# RX.net
KiCad netlist of a schematic drawn in EAGLE
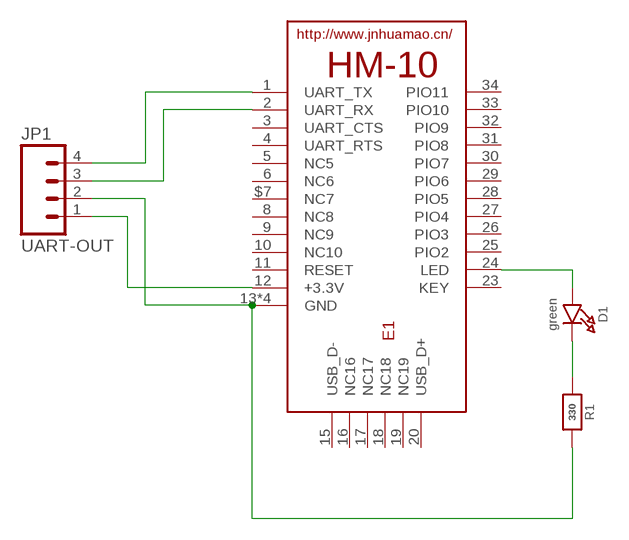
[diagram p0: schematic, sheet 1]

(export (version "E")
  (design (tool "Eeschema 10.0.6"))
  (components
    (comp (ref "D1")
      (value "green")
      (footprint "eagle-import:CHIPLED_0805_NOOUTLINE")
      (libsource (lib "eagle-import") (part "LED0805_NOOUTLINE"))
    )
    (comp (ref "E1")
      (value "HM-10-BOARD")
      (footprint "eagle-import:26.9X13X2.2_BOARD")
      (libsource (lib "eagle-import") (part "HM-10-BOARD"))
    )
    (comp (ref "JP1")
      (value "UART-OUT")
      (footprint "eagle-import:1X04")
      (libsource (lib "eagle-import") (part "M04PTH"))
    )
    (comp (ref "R1")
      (value "330")
      (footprint "eagle-import:0805-NO")
      (libsource (lib "eagle-import") (part "RESISTOR0805_NOOUTLINE"))
    )
  )
  (nets
    (net (code "1") (name "Net-(D1-PadC)") (class "Default")
      (node (ref "D1") (pin "C") (pinfunction "C_C") (pintype "passive"))
      (node (ref "R1") (pin "1") (pinfunction "1_1") (pintype "passive"))
    )
    (net (code "2") (name "Net-(E1-+3.3V)") (class "Default")
      (node (ref "E1") (pin "12") (pinfunction "+3.3V_12") (pintype "bidirectional"))
      (node (ref "JP1") (pin "1") (pinfunction "1_1") (pintype "passive"))
    )
    (net (code "3") (name "Net-(E1-GND-Pad13)") (class "Default")
      (node (ref "E1") (pin "13") (pinfunction "GND_13") (pintype "bidirectional"))
      (node (ref "E1") (pin "14") (pinfunction "GND_14") (pintype "bidirectional"))
      (node (ref "E1") (pin "21") (pinfunction "GND_21") (pintype "bidirectional"))
      (node (ref "E1") (pin "22") (pinfunction "GND_22") (pintype "bidirectional"))
      (node (ref "JP1") (pin "2") (pinfunction "2_2") (pintype "passive"))
      (node (ref "R1") (pin "2") (pinfunction "2_2") (pintype "passive"))
    )
    (net (code "4") (name "Net-(E1-LED)") (class "Default")
      (node (ref "D1") (pin "A") (pinfunction "A_A") (pintype "passive"))
      (node (ref "E1") (pin "24") (pinfunction "LED_24") (pintype "bidirectional"))
    )
    (net (code "5") (name "Net-(E1-UART_RX)") (class "Default")
      (node (ref "E1") (pin "2") (pinfunction "UART_RX_2") (pintype "bidirectional"))
      (node (ref "JP1") (pin "3") (pinfunction "3_3") (pintype "passive"))
    )
    (net (code "6") (name "Net-(E1-UART_TX)") (class "Default")
      (node (ref "E1") (pin "1") (pinfunction "UART_TX_1") (pintype "bidirectional"))
      (node (ref "JP1") (pin "4") (pinfunction "4_4") (pintype "passive"))
    )
    (net (code "7") (name "unconnected-(E1-KEY-Pad23)") (class "Default")
      (node (ref "E1") (pin "23") (pinfunction "KEY_23") (pintype "bidirectional"))
    )
    (net (code "8") (name "unconnected-(E1-NC5-Pad5)") (class "Default")
      (node (ref "E1") (pin "5") (pinfunction "NC5_5") (pintype "bidirectional"))
    )
    (net (code "9") (name "unconnected-(E1-NC6-Pad6)") (class "Default")
      (node (ref "E1") (pin "6") (pinfunction "NC6_6") (pintype "bidirectional"))
    )
    (net (code "10") (name "unconnected-(E1-NC7-Pad$7)") (class "Default")
      (node (ref "E1") (pin "$7") (pinfunction "NC7_$7") (pintype "bidirectional"))
    )
    (net (code "11") (name "unconnected-(E1-NC8-Pad8)") (class "Default")
      (node (ref "E1") (pin "8") (pinfunction "NC8_8") (pintype "bidirectional"))
    )
    (net (code "12") (name "unconnected-(E1-NC9-Pad9)") (class "Default")
      (node (ref "E1") (pin "9") (pinfunction "NC9_9") (pintype "bidirectional"))
    )
    (net (code "13") (name "unconnected-(E1-NC10-Pad10)") (class "Default")
      (node (ref "E1") (pin "10") (pinfunction "NC10_10") (pintype "bidirectional"))
    )
    (net (code "14") (name "unconnected-(E1-NC16-Pad16)") (class "Default")
      (node (ref "E1") (pin "16") (pinfunction "NC16_16") (pintype "bidirectional"))
    )
    (net (code "15") (name "unconnected-(E1-NC17-Pad17)") (class "Default")
      (node (ref "E1") (pin "17") (pinfunction "NC17_17") (pintype "bidirectional"))
    )
    (net (code "16") (name "unconnected-(E1-NC18-Pad18)") (class "Default")
      (node (ref "E1") (pin "18") (pinfunction "NC18_18") (pintype "bidirectional"))
    )
    (net (code "17") (name "unconnected-(E1-NC19-Pad19)") (class "Default")
      (node (ref "E1") (pin "19") (pinfunction "NC19_19") (pintype "bidirectional"))
    )
    (net (code "18") (name "unconnected-(E1-PIO2-Pad25)") (class "Default")
      (node (ref "E1") (pin "25") (pinfunction "PIO2_25") (pintype "bidirectional"))
    )
    (net (code "19") (name "unconnected-(E1-PIO3-Pad26)") (class "Default")
      (node (ref "E1") (pin "26") (pinfunction "PIO3_26") (pintype "bidirectional"))
    )
    (net (code "20") (name "unconnected-(E1-PIO4-Pad27)") (class "Default")
      (node (ref "E1") (pin "27") (pinfunction "PIO4_27") (pintype "bidirectional"))
    )
    (net (code "21") (name "unconnected-(E1-PIO5-Pad28)") (class "Default")
      (node (ref "E1") (pin "28") (pinfunction "PIO5_28") (pintype "bidirectional"))
    )
    (net (code "22") (name "unconnected-(E1-PIO6-Pad29)") (class "Default")
      (node (ref "E1") (pin "29") (pinfunction "PIO6_29") (pintype "bidirectional"))
    )
    (net (code "23") (name "unconnected-(E1-PIO7-Pad30)") (class "Default")
      (node (ref "E1") (pin "30") (pinfunction "PIO7_30") (pintype "bidirectional"))
    )
    (net (code "24") (name "unconnected-(E1-PIO8-Pad31)") (class "Default")
      (node (ref "E1") (pin "31") (pinfunction "PIO8_31") (pintype "bidirectional"))
    )
    (net (code "25") (name "unconnected-(E1-PIO9-Pad32)") (class "Default")
      (node (ref "E1") (pin "32") (pinfunction "PIO9_32") (pintype "bidirectional"))
    )
    (net (code "26") (name "unconnected-(E1-PIO10-Pad33)") (class "Default")
      (node (ref "E1") (pin "33") (pinfunction "PIO10_33") (pintype "bidirectional"))
    )
    (net (code "27") (name "unconnected-(E1-PIO11-Pad34)") (class "Default")
      (node (ref "E1") (pin "34") (pinfunction "PIO11_34") (pintype "bidirectional"))
    )
    (net (code "28") (name "unconnected-(E1-RESET-Pad11)") (class "Default")
      (node (ref "E1") (pin "11") (pinfunction "RESET_11") (pintype "bidirectional"))
    )
    (net (code "29") (name "unconnected-(E1-UART_CTS-Pad3)") (class "Default")
      (node (ref "E1") (pin "3") (pinfunction "UART_CTS_3") (pintype "bidirectional"))
    )
    (net (code "30") (name "unconnected-(E1-UART_RTS-Pad4)") (class "Default")
      (node (ref "E1") (pin "4") (pinfunction "UART_RTS_4") (pintype "bidirectional"))
    )
    (net (code "31") (name "unconnected-(E1-USB_D+-Pad20)") (class "Default")
      (node (ref "E1") (pin "20") (pinfunction "USB_D+_20") (pintype "bidirectional"))
    )
    (net (code "32") (name "unconnected-(E1-USB_D--Pad15)") (class "Default")
      (node (ref "E1") (pin "15") (pinfunction "USB_D-_15") (pintype "bidirectional"))
    )
  )
)
